# RFM69_USB_Gateway.net
KiCad netlist of a schematic drawn in EAGLE
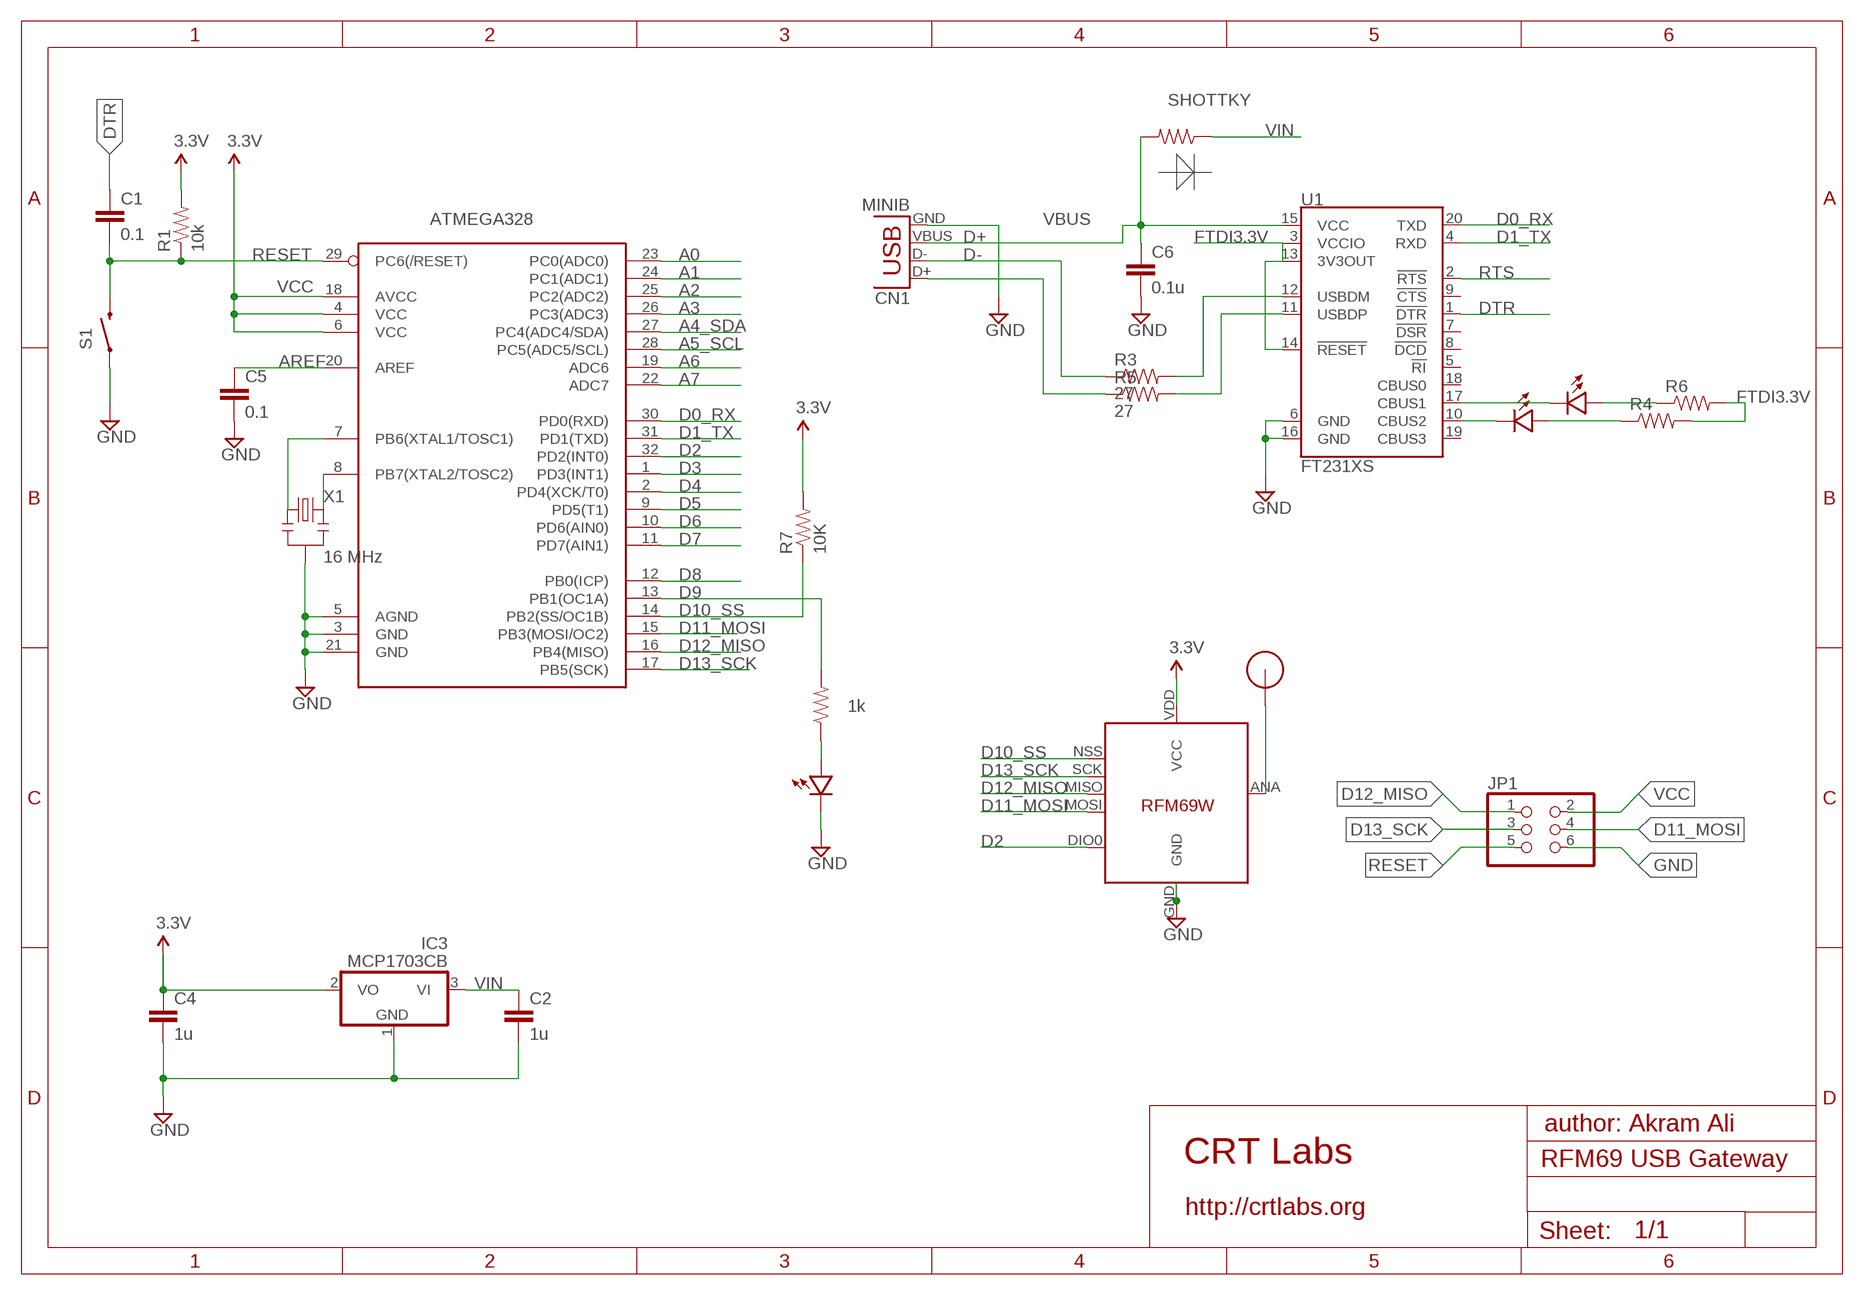
[diagram p0: schematic, sheet 1]

(export (version "E")
  (design (tool "Eeschema 10.0.6"))
  (components
    (comp (ref "ATMEGA328")
      (value "ATMega-328")
      (footprint "eagle-import:TQFP32-08")
      (libsource (lib "eagle-import") (part "ATMEGA168/328TQFP32"))
    )
    (comp (ref "C1")
      (value "0.1")
      (footprint "eagle-import:0805")
      (libsource (lib "eagle-import") (part "SparkFun_CAP0805"))
    )
    (comp (ref "C2")
      (value "1u")
      (footprint "eagle-import:0805")
      (libsource (lib "eagle-import") (part "SparkFun_CAP0805"))
    )
    (comp (ref "C4")
      (value "1u")
      (footprint "eagle-import:0805")
      (libsource (lib "eagle-import") (part "CAP0805"))
    )
    (comp (ref "C5")
      (value "0.1")
      (footprint "eagle-import:0805")
      (libsource (lib "eagle-import") (part "SparkFun_CAP0805"))
    )
    (comp (ref "C6")
      (value "0.1u")
      (footprint "eagle-import:0805")
      (libsource (lib "eagle-import") (part "SparkFun_CAP0805"))
    )
    (comp (ref "CN1")
      (value "MINIB")
      (footprint "eagle-import:USB-A-H")
      (libsource (lib "eagle-import") (part "USB-A-H"))
    )
    (comp (ref "D")
      (value "SHOTTKY")
      (footprint "eagle-import:0805")
      (libsource (lib "eagle-import") (part "RESISTOR0805"))
    )
    (comp (ref "IC3")
      (value "MCP1703CB")
      (footprint "eagle-import:SOT23")
      (libsource (lib "eagle-import") (part "MCP1703CB"))
    )
    (comp (ref "JP1")
      (value "PINHD-2X3")
      (footprint "eagle-import:2X03")
      (libsource (lib "eagle-import") (part "PINHD-2X3"))
    )
    (comp (ref "R1")
      (value "10k")
      (footprint "eagle-import:0805")
      (libsource (lib "eagle-import") (part "RESISTOR0805"))
    )
    (comp (ref "R2")
      (value "1k")
      (footprint "eagle-import:0805")
      (libsource (lib "eagle-import") (part "SparkFun_RESISTOR0805-RES"))
    )
    (comp (ref "R3")
      (value "27")
      (footprint "eagle-import:0805")
      (libsource (lib "eagle-import") (part "SparkFun_RESISTOR0805-RES"))
    )
    (comp (ref "R4")
      (value "RESISTOR0805-RES")
      (footprint "eagle-import:0805")
      (libsource (lib "eagle-import") (part "SparkFun_RESISTOR0805-RES"))
    )
    (comp (ref "R5")
      (value "27")
      (footprint "eagle-import:0805")
      (libsource (lib "eagle-import") (part "SparkFun_RESISTOR0805-RES"))
    )
    (comp (ref "R6")
      (value "RESISTOR0805-RES")
      (footprint "eagle-import:0805")
      (libsource (lib "eagle-import") (part "SparkFun_RESISTOR0805-RES"))
    )
    (comp (ref "R7")
      (value "10K")
      (footprint "eagle-import:0805")
      (libsource (lib "eagle-import") (part "SparkFun_RESISTOR0805-RES"))
    )
    (comp (ref "S1")
      (value "SWITCH-MOMENTARY-2SMD-ALT01")
      (footprint "eagle-import:TACTILE-SWITCH-SMD-ALT01")
      (libsource (lib "eagle-import") (part "SWITCH-MOMENTARY-2SMD-ALT01"))
    )
    (comp (ref "U$1")
      (value "RFM12B_ANTENNA")
      (footprint "eagle-import:RFM12B-ANTENNA")
      (libsource (lib "eagle-import") (part "RFM12B_ANTENNA"))
    )
    (comp (ref "U$2")
      (value "LED0805")
      (footprint "eagle-import:0805-LED")
      (libsource (lib "eagle-import") (part "LED0805"))
    )
    (comp (ref "U$4")
      (value "LED0805")
      (footprint "eagle-import:0805-LED")
      (libsource (lib "eagle-import") (part "LED0805"))
    )
    (comp (ref "U$5")
      (value "RFM69")
      (footprint "eagle-import:RFM69W-MINPADS")
      (libsource (lib "eagle-import") (part "RFM69"))
    )
    (comp (ref "U$7")
      (value "LED0805")
      (footprint "eagle-import:0805-LED")
      (libsource (lib "eagle-import") (part "LED0805"))
    )
    (comp (ref "U1")
      (value "FT231XS")
      (footprint "eagle-import:SSOP20_L")
      (libsource (lib "eagle-import") (part "FT231XS"))
    )
    (comp (ref "X1")
      (value "16 MHz")
      (footprint "eagle-import:RESONATOR-SMD")
      (libsource (lib "eagle-import") (part "RESONATORSMD"))
    )
  )
  (nets
    (net (code "1") (name "/A0") (class "Default")
      (node (ref "ATMEGA328") (pin "23") (pinfunction "PC0(ADC0)_23") (pintype "bidirectional"))
    )
    (net (code "2") (name "/A1") (class "Default")
      (node (ref "ATMEGA328") (pin "24") (pinfunction "PC1(ADC1)_24") (pintype "bidirectional"))
    )
    (net (code "3") (name "/A2") (class "Default")
      (node (ref "ATMEGA328") (pin "25") (pinfunction "PC2(ADC2)_25") (pintype "bidirectional"))
    )
    (net (code "4") (name "/A3") (class "Default")
      (node (ref "ATMEGA328") (pin "26") (pinfunction "PC3(ADC3)_26") (pintype "bidirectional"))
    )
    (net (code "5") (name "/A4_SDA") (class "Default")
      (node (ref "ATMEGA328") (pin "27") (pinfunction "PC4(ADC4/SDA)_27") (pintype "bidirectional"))
    )
    (net (code "6") (name "/A5_SCL") (class "Default")
      (node (ref "ATMEGA328") (pin "28") (pinfunction "PC5(ADC5/SCL)_28") (pintype "bidirectional"))
    )
    (net (code "7") (name "/A6") (class "Default")
      (node (ref "ATMEGA328") (pin "19") (pinfunction "ADC6_19") (pintype "bidirectional"))
    )
    (net (code "8") (name "/A7") (class "Default")
      (node (ref "ATMEGA328") (pin "22") (pinfunction "ADC7_22") (pintype "bidirectional"))
    )
    (net (code "9") (name "/AREF") (class "Default")
      (node (ref "ATMEGA328") (pin "20") (pinfunction "AREF_20") (pintype "bidirectional"))
      (node (ref "C5") (pin "1") (pinfunction "1_1") (pintype "passive"))
    )
    (net (code "10") (name "/D+") (class "Default")
      (node (ref "CN1") (pin "D+") (pinfunction "D+_D+") (pintype "bidirectional"))
      (node (ref "R5") (pin "1") (pinfunction "1_1") (pintype "passive"))
    )
    (net (code "11") (name "/D-") (class "Default")
      (node (ref "CN1") (pin "D-") (pinfunction "D-_D-") (pintype "bidirectional"))
      (node (ref "R3") (pin "1") (pinfunction "1_1") (pintype "passive"))
    )
    (net (code "12") (name "/D0_RX") (class "Default")
      (node (ref "ATMEGA328") (pin "30") (pinfunction "PD0(RXD)_30") (pintype "bidirectional"))
      (node (ref "U1") (pin "20") (pinfunction "TXD_20") (pintype "bidirectional"))
    )
    (net (code "13") (name "/D1_TX") (class "Default")
      (node (ref "ATMEGA328") (pin "31") (pinfunction "PD1(TXD)_31") (pintype "bidirectional"))
      (node (ref "U1") (pin "4") (pinfunction "RXD_4") (pintype "bidirectional"))
    )
    (net (code "14") (name "/D2") (class "Default")
      (node (ref "ATMEGA328") (pin "32") (pinfunction "PD2(INT0)_32") (pintype "bidirectional"))
      (node (ref "U$5") (pin "DIO0") (pinfunction "DIO0_DIO0") (pintype "open_collector"))
    )
    (net (code "15") (name "/D3") (class "Default")
      (node (ref "ATMEGA328") (pin "1") (pinfunction "PD3(INT1)_1") (pintype "bidirectional"))
    )
    (net (code "16") (name "/D4") (class "Default")
      (node (ref "ATMEGA328") (pin "2") (pinfunction "PD4(XCK/T0)_2") (pintype "bidirectional"))
    )
    (net (code "17") (name "/D5") (class "Default")
      (node (ref "ATMEGA328") (pin "9") (pinfunction "PD5(T1)_9") (pintype "bidirectional"))
    )
    (net (code "18") (name "/D6") (class "Default")
      (node (ref "ATMEGA328") (pin "10") (pinfunction "PD6(AIN0)_10") (pintype "bidirectional"))
    )
    (net (code "19") (name "/D7") (class "Default")
      (node (ref "ATMEGA328") (pin "11") (pinfunction "PD7(AIN1)_11") (pintype "bidirectional"))
    )
    (net (code "20") (name "/D8") (class "Default")
      (node (ref "ATMEGA328") (pin "12") (pinfunction "PB0(ICP)_12") (pintype "bidirectional"))
    )
    (net (code "21") (name "/D9") (class "Default")
      (node (ref "ATMEGA328") (pin "13") (pinfunction "PB1(OC1A)_13") (pintype "bidirectional"))
      (node (ref "R2") (pin "2") (pinfunction "2_2") (pintype "passive"))
    )
    (net (code "22") (name "/D10_SS") (class "Default")
      (node (ref "ATMEGA328") (pin "14") (pinfunction "PB2(SS/OC1B)_14") (pintype "bidirectional"))
      (node (ref "R7") (pin "1") (pinfunction "1_1") (pintype "passive"))
      (node (ref "U$5") (pin "NSS") (pinfunction "SEL_NSS") (pintype "input"))
    )
    (net (code "23") (name "/FTDI3.3V") (class "Default")
      (node (ref "R4") (pin "2") (pinfunction "2_2") (pintype "passive"))
      (node (ref "R6") (pin "2") (pinfunction "2_2") (pintype "passive"))
      (node (ref "U1") (pin "13") (pinfunction "3V3OUT_13") (pintype "bidirectional"))
      (node (ref "U1") (pin "14") (pinfunction "~{RESET}_14") (pintype "bidirectional"))
      (node (ref "U1") (pin "3") (pinfunction "VCCIO_3") (pintype "bidirectional"))
    )
    (net (code "24") (name "/RTS") (class "Default")
      (node (ref "U1") (pin "2") (pinfunction "~{RTS}_2") (pintype "bidirectional"))
    )
    (net (code "25") (name "/VBUS") (class "Default")
      (node (ref "C6") (pin "1") (pinfunction "1_1") (pintype "passive"))
      (node (ref "CN1") (pin "VBUS") (pinfunction "VBUS_VBUS") (pintype "bidirectional"))
      (node (ref "D") (pin "2") (pinfunction "2_2") (pintype "passive"))
      (node (ref "U1") (pin "15") (pinfunction "VCC_15") (pintype "bidirectional"))
    )
    (net (code "26") (name "/VIN") (class "Default")
      (node (ref "C2") (pin "1") (pinfunction "1_1") (pintype "passive"))
      (node (ref "D") (pin "1") (pinfunction "1_1") (pintype "passive"))
      (node (ref "IC3") (pin "3") (pinfunction "VI_3") (pintype "input"))
    )
    (net (code "27") (name "D11_MOSI") (class "Default")
      (node (ref "ATMEGA328") (pin "15") (pinfunction "PB3(MOSI/OC2)_15") (pintype "bidirectional"))
      (node (ref "JP1") (pin "4") (pinfunction "4_4") (pintype "passive"))
      (node (ref "U$5") (pin "MOSI") (pinfunction "MOSI_MOSI") (pintype "output"))
    )
    (net (code "28") (name "D12_MISO") (class "Default")
      (node (ref "ATMEGA328") (pin "16") (pinfunction "PB4(MISO)_16") (pintype "bidirectional"))
      (node (ref "JP1") (pin "1") (pinfunction "1_1") (pintype "passive"))
      (node (ref "U$5") (pin "MISO") (pinfunction "MISO_MISO") (pintype "input"))
    )
    (net (code "29") (name "D13_SCK") (class "Default")
      (node (ref "ATMEGA328") (pin "17") (pinfunction "PB5(SCK)_17") (pintype "bidirectional"))
      (node (ref "JP1") (pin "3") (pinfunction "3_3") (pintype "passive"))
      (node (ref "U$5") (pin "SCK") (pinfunction "SCK_SCK") (pintype "input"))
    )
    (net (code "30") (name "DTR") (class "Default")
      (node (ref "C1") (pin "1") (pinfunction "1_1") (pintype "passive"))
      (node (ref "U1") (pin "1") (pinfunction "~{DTR}_1") (pintype "bidirectional"))
    )
    (net (code "31") (name "GND") (class "Default")
      (node (ref "ATMEGA328") (pin "21") (pinfunction "GND_21") (pintype "bidirectional"))
      (node (ref "ATMEGA328") (pin "3") (pinfunction "GND_3") (pintype "bidirectional"))
      (node (ref "ATMEGA328") (pin "5") (pinfunction "AGND_5") (pintype "bidirectional"))
      (node (ref "C2") (pin "2") (pinfunction "2_2") (pintype "passive"))
      (node (ref "C4") (pin "2") (pinfunction "2_2") (pintype "passive"))
      (node (ref "C5") (pin "2") (pinfunction "2_2") (pintype "passive"))
      (node (ref "C6") (pin "2") (pinfunction "2_2") (pintype "passive"))
      (node (ref "CN1") (pin "GND") (pinfunction "GND_GND") (pintype "bidirectional"))
      (node (ref "IC3") (pin "1") (pinfunction "GND_1") (pintype "passive"))
      (node (ref "JP1") (pin "6") (pinfunction "6_6") (pintype "passive"))
      (node (ref "S1") (pin "1") (pinfunction "1_1") (pintype "passive"))
      (node (ref "S1") (pin "2") (pinfunction "1_2") (pintype "passive"))
      (node (ref "U$2") (pin "MINUS") (pinfunction "MINUS_MINUS") (pintype "passive"))
      (node (ref "U$5") (pin "GND") (pinfunction "GND_GND") (pintype "power_in"))
      (node (ref "U1") (pin "16") (pinfunction "GND_16") (pintype "bidirectional"))
      (node (ref "U1") (pin "6") (pinfunction "GND_6") (pintype "bidirectional"))
      (node (ref "X1") (pin "2") (pinfunction "2_2") (pintype "passive"))
    )
    (net (code "32") (name "Net-(ATMEGA328-PB6(XTAL1{slash}TOSC1))") (class "Default")
      (node (ref "ATMEGA328") (pin "7") (pinfunction "PB6(XTAL1/TOSC1)_7") (pintype "bidirectional"))
      (node (ref "X1") (pin "1") (pinfunction "1_1") (pintype "passive"))
    )
    (net (code "33") (name "Net-(ATMEGA328-PB7(XTAL2{slash}TOSC2))") (class "Default")
      (node (ref "ATMEGA328") (pin "8") (pinfunction "PB7(XTAL2/TOSC2)_8") (pintype "bidirectional"))
      (node (ref "X1") (pin "3") (pinfunction "3_3") (pintype "passive"))
    )
    (net (code "34") (name "Net-(R2-Pad1)") (class "Default")
      (node (ref "R2") (pin "1") (pinfunction "1_1") (pintype "passive"))
      (node (ref "U$2") (pin "PLUS") (pinfunction "PLUS_PLUS") (pintype "passive"))
    )
    (net (code "35") (name "Net-(R4-Pad1)") (class "Default")
      (node (ref "R4") (pin "1") (pinfunction "1_1") (pintype "passive"))
      (node (ref "U$7") (pin "PLUS") (pinfunction "PLUS_PLUS") (pintype "passive"))
    )
    (net (code "36") (name "Net-(R6-Pad1)") (class "Default")
      (node (ref "R6") (pin "1") (pinfunction "1_1") (pintype "passive"))
      (node (ref "U$4") (pin "PLUS") (pinfunction "PLUS_PLUS") (pintype "passive"))
    )
    (net (code "37") (name "Net-(U$1-1)") (class "Default")
      (node (ref "U$1") (pin "P$1") (pinfunction "1_P$1") (pintype "bidirectional"))
      (node (ref "U$5") (pin "ANA") (pinfunction "ANT_ANA") (pintype "passive"))
    )
    (net (code "38") (name "Net-(U1-CBUS1)") (class "Default")
      (node (ref "U$4") (pin "MINUS") (pinfunction "MINUS_MINUS") (pintype "passive"))
      (node (ref "U1") (pin "17") (pinfunction "CBUS1_17") (pintype "bidirectional"))
    )
    (net (code "39") (name "Net-(U1-CBUS2)") (class "Default")
      (node (ref "U$7") (pin "MINUS") (pinfunction "MINUS_MINUS") (pintype "passive"))
      (node (ref "U1") (pin "10") (pinfunction "CBUS2_10") (pintype "bidirectional"))
    )
    (net (code "40") (name "Net-(U1-USBDM)") (class "Default")
      (node (ref "R3") (pin "2") (pinfunction "2_2") (pintype "passive"))
      (node (ref "U1") (pin "12") (pinfunction "USBDM_12") (pintype "bidirectional"))
    )
    (net (code "41") (name "Net-(U1-USBDP)") (class "Default")
      (node (ref "R5") (pin "2") (pinfunction "2_2") (pintype "passive"))
      (node (ref "U1") (pin "11") (pinfunction "USBDP_11") (pintype "bidirectional"))
    )
    (net (code "42") (name "RESET") (class "Default")
      (node (ref "ATMEGA328") (pin "29") (pinfunction "PC6(/RESET)_29") (pintype "bidirectional"))
      (node (ref "C1") (pin "2") (pinfunction "2_2") (pintype "passive"))
      (node (ref "JP1") (pin "5") (pinfunction "5_5") (pintype "passive"))
      (node (ref "R1") (pin "1") (pinfunction "1_1") (pintype "passive"))
      (node (ref "S1") (pin "3") (pinfunction "2_3") (pintype "passive"))
      (node (ref "S1") (pin "4") (pinfunction "2_4") (pintype "passive"))
    )
    (net (code "43") (name "VCC") (class "Default")
      (node (ref "ATMEGA328") (pin "18") (pinfunction "AVCC_18") (pintype "bidirectional"))
      (node (ref "ATMEGA328") (pin "4") (pinfunction "VCC_4") (pintype "bidirectional"))
      (node (ref "ATMEGA328") (pin "6") (pinfunction "VCC_6") (pintype "bidirectional"))
      (node (ref "C4") (pin "1") (pinfunction "1_1") (pintype "passive"))
      (node (ref "IC3") (pin "2") (pinfunction "VO_2") (pintype "passive"))
      (node (ref "JP1") (pin "2") (pinfunction "2_2") (pintype "passive"))
      (node (ref "R1") (pin "2") (pinfunction "2_2") (pintype "passive"))
      (node (ref "R7") (pin "2") (pinfunction "2_2") (pintype "passive"))
      (node (ref "U$5") (pin "VDD") (pinfunction "VCC_VDD") (pintype "power_in"))
    )
    (net (code "44") (name "unconnected-(U1-CBUS0-Pad18)") (class "Default")
      (node (ref "U1") (pin "18") (pinfunction "CBUS0_18") (pintype "bidirectional"))
    )
    (net (code "45") (name "unconnected-(U1-CBUS3-Pad19)") (class "Default")
      (node (ref "U1") (pin "19") (pinfunction "CBUS3_19") (pintype "bidirectional"))
    )
    (net (code "46") (name "unconnected-(U1-~{CTS}-Pad9)") (class "Default")
      (node (ref "U1") (pin "9") (pinfunction "~{CTS}_9") (pintype "bidirectional"))
    )
    (net (code "47") (name "unconnected-(U1-~{DCD}-Pad8)") (class "Default")
      (node (ref "U1") (pin "8") (pinfunction "~{DCD}_8") (pintype "bidirectional"))
    )
    (net (code "48") (name "unconnected-(U1-~{DSR}-Pad7)") (class "Default")
      (node (ref "U1") (pin "7") (pinfunction "~{DSR}_7") (pintype "bidirectional"))
    )
    (net (code "49") (name "unconnected-(U1-~{RI}-Pad5)") (class "Default")
      (node (ref "U1") (pin "5") (pinfunction "~{RI}_5") (pintype "bidirectional"))
    )
  )
)
